# nearsens-schematic-source-2026-05-25-v0_.net
KiCad netlist of a schematic drawn in EasyEDA
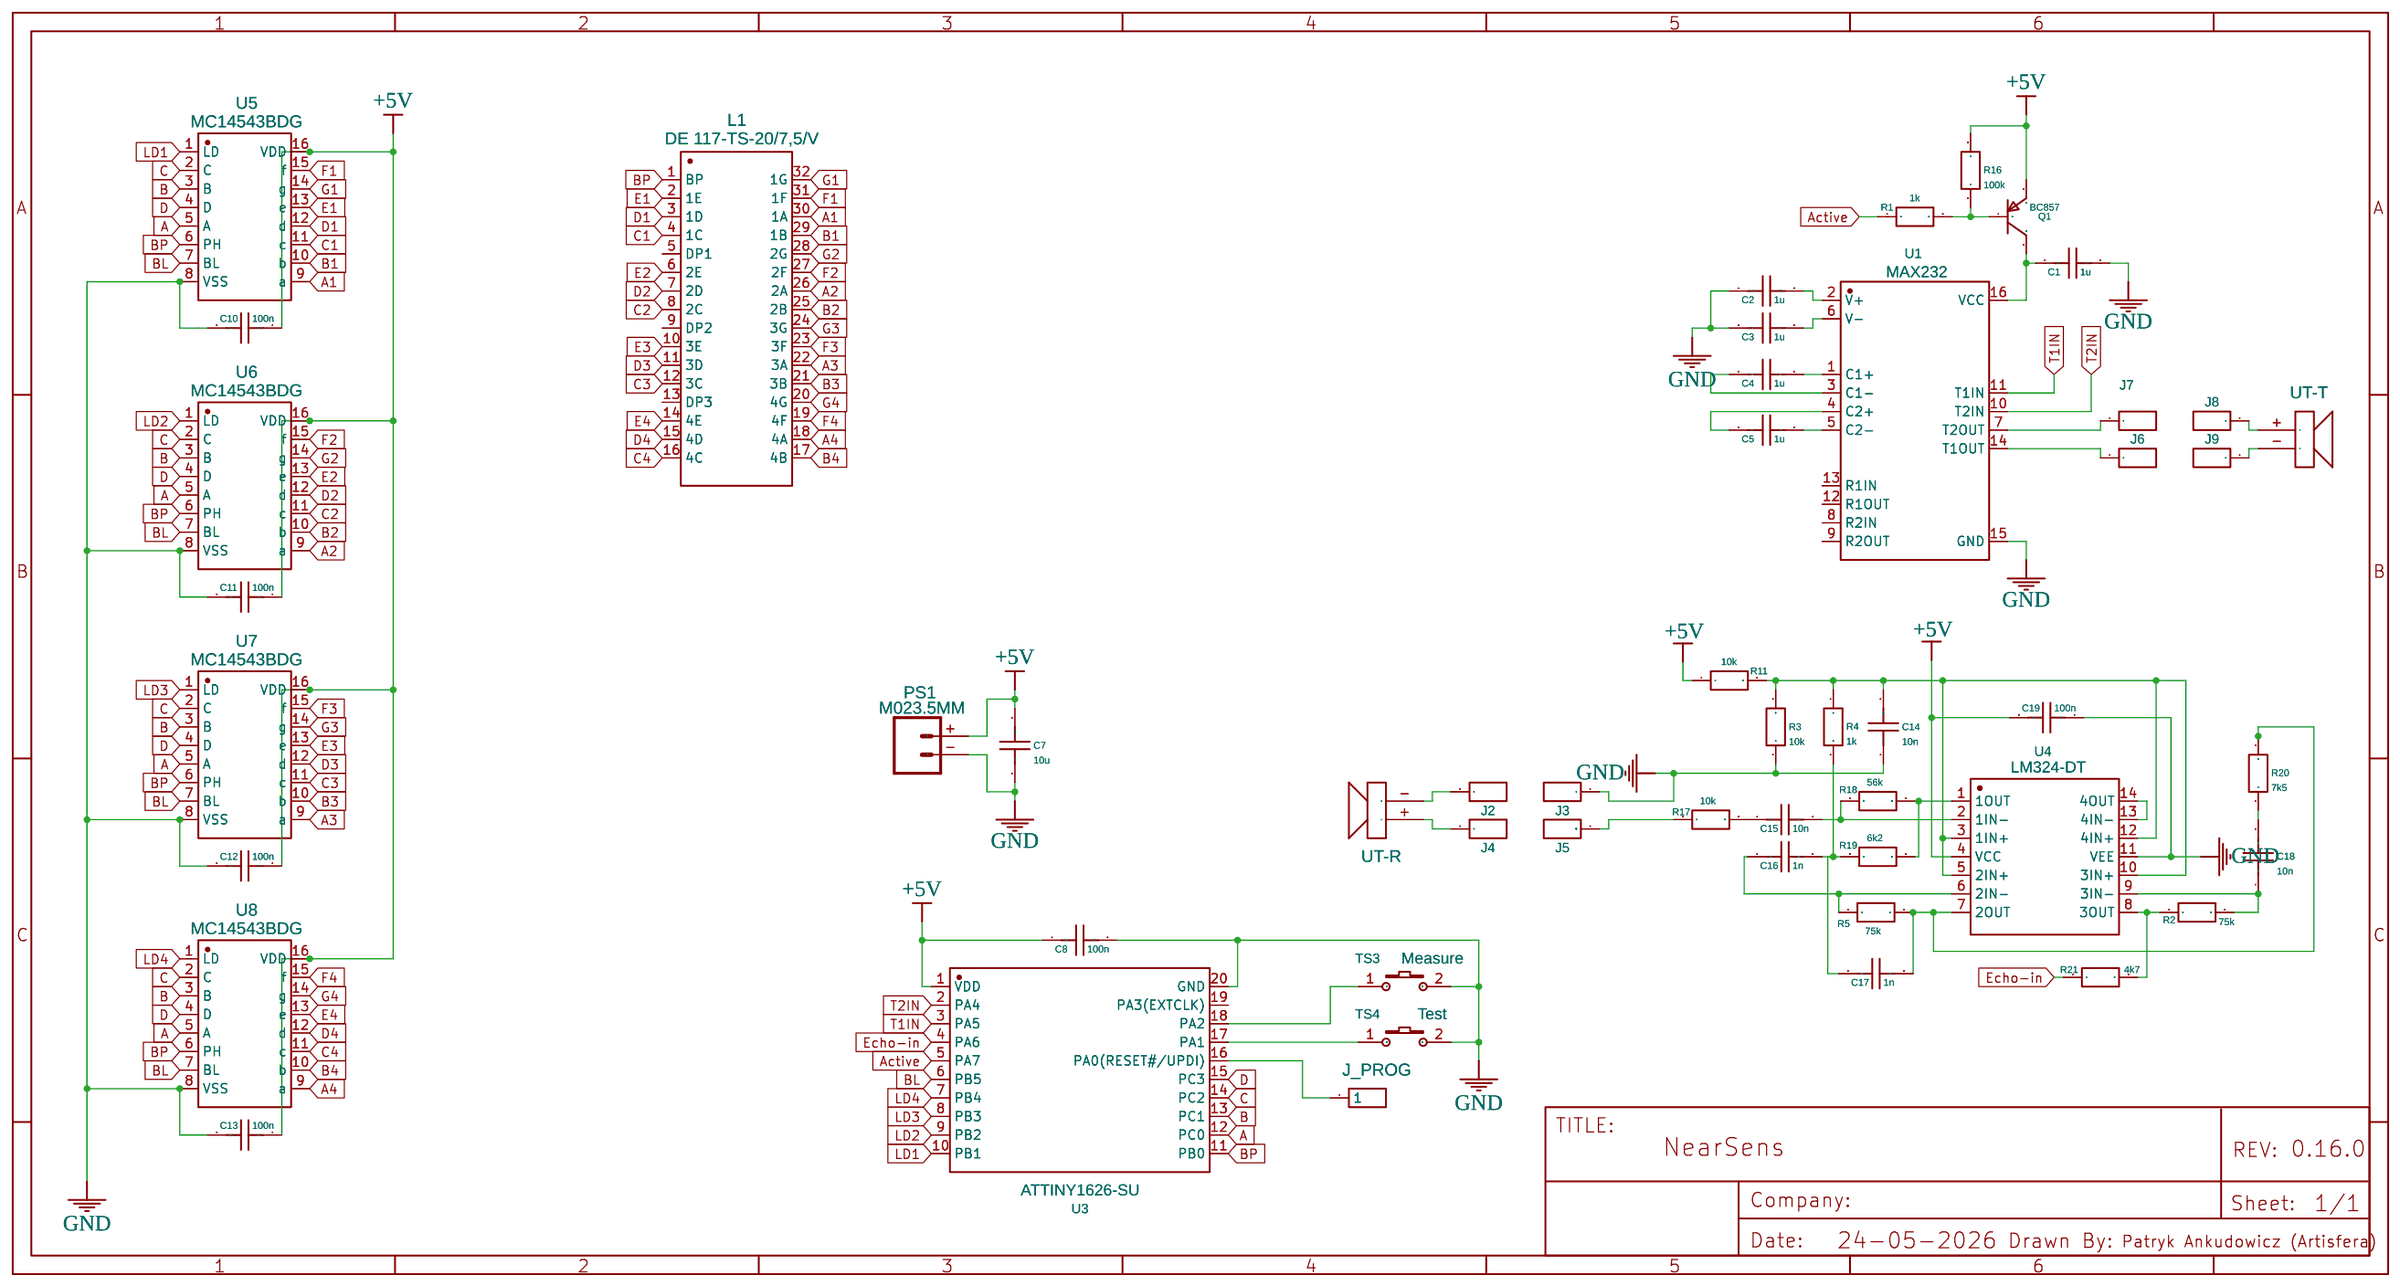
[diagram p0: schematic sheet]

(export (version "E")
  (design (tool "Eeschema 10.0.6"))
  (components
    (comp (ref "C1") (value "1u") (libsource (lib "") (part "C_0603_US_1")))
    (comp (ref "C2") (value "1u") (libsource (lib "") (part "C_0603_US_1")))
    (comp (ref "C3") (value "1u") (libsource (lib "") (part "C_0603_US_1")))
    (comp (ref "C4") (value "1u") (libsource (lib "") (part "C_0603_US_1")))
    (comp (ref "C5") (value "1u") (libsource (lib "") (part "C_0603_US_1")))
    (comp (ref "C7") (value "10u") (libsource (lib "") (part "C_0603_US_3")))
    (comp (ref "C8") (value "100n") (libsource (lib "") (part "C_0603_US_1")))
    (comp (ref "C10") (value "100n") (libsource (lib "") (part "C_0603_US")))
    (comp (ref "C11") (value "100n") (libsource (lib "") (part "C_0603_US")))
    (comp (ref "C12") (value "100n") (libsource (lib "") (part "C_0603_US")))
    (comp (ref "C13") (value "100n") (libsource (lib "") (part "C_0603_US")))
    (comp (ref "C14") (value "10n") (libsource (lib "") (part "C_0603_US_2")))
    (comp (ref "C15") (value "10n") (libsource (lib "") (part "C_0603_US_1")))
    (comp (ref "C16") (value "1n") (libsource (lib "") (part "C_0603_US_1")))
    (comp (ref "C17") (value "1n") (libsource (lib "") (part "C_0603_US_1")))
    (comp (ref "C18") (value "10n") (libsource (lib "") (part "C_0603_US_2")))
    (comp (ref "C19") (value "100n") (libsource (lib "") (part "C_0603_US")))
    (comp (ref "J2") (value "HDR-M-2.54_1x1") (libsource (lib "") (part "HDR-M-2.54_1x1_1")))
    (comp (ref "J3") (value "HDR-M-2.54_1x1") (libsource (lib "") (part "HDR-M-2.54_1x1")))
    (comp (ref "J4") (value "HDR-M-2.54_1x1") (libsource (lib "") (part "HDR-M-2.54_1x1_1")))
    (comp (ref "J5") (value "HDR-M-2.54_1x1") (libsource (lib "") (part "HDR-M-2.54_1x1_2")))
    (comp (ref "J6") (value "HDR-M-2.54_1x1") (libsource (lib "") (part "HDR-M-2.54_1x1_1")))
    (comp (ref "J7") (value "HDR-M-2.54_1x1") (libsource (lib "") (part "HDR-M-2.54_1x1_1")))
    (comp (ref "J8") (value "HDR-M-2.54_1x1") (libsource (lib "") (part "HDR-M-2.54_1x1")))
    (comp (ref "J9") (value "HDR-M-2.54_1x1") (libsource (lib "") (part "HDR-M-2.54_1x1")))
    (comp (ref "J_PROG") (value "Programming") (libsource (lib "") (part "HDR-M-2.54_1x1_3")))
    (comp (ref "L1")
      (value "DE 117-TS-20/7,5/V")
      (fields (field (name "Manufacturer") "DISPLAY ELEKTRONIK"))
      (libsource (lib "") (part "DE 117-TS-20/7,5/V DISPLAY ELEKTRONIK - Display LCD"))
    )
    (comp (ref "PS1") (value "M023.5MM") (libsource (lib "") (part "M023.5MM")))
    (comp (ref "Q1")
      (value "BC857")
      (fields
        (field (name "Manufacturer Part") "BC557(RANGE:420-800)")
        (field (name "Manufacturer") "CJ(江苏长电/长晶)")
      )
      (libsource (lib "") (part "BC557"))
    )
    (comp (ref "R1") (value "1k") (libsource (lib "") (part "R_0603_EU")))
    (comp (ref "R2") (value "75k") (libsource (lib "") (part "R_0603_EU")))
    (comp (ref "R3") (value "10k") (libsource (lib "") (part "R_0603_EU_1")))
    (comp (ref "R4") (value "1k") (libsource (lib "") (part "R_0603_EU_2")))
    (comp (ref "R5") (value "75k") (libsource (lib "") (part "R_0603_EU")))
    (comp (ref "R11") (value "10k") (libsource (lib "") (part "R_0603_EU")))
    (comp (ref "R16") (value "100k") (libsource (lib "") (part "R_0603_EU_1")))
    (comp (ref "R17") (value "10k") (libsource (lib "") (part "R_0603_EU")))
    (comp (ref "R18") (value "56k") (libsource (lib "") (part "R_0603_EU")))
    (comp (ref "R19") (value "6k2") (libsource (lib "") (part "R_0603_EU")))
    (comp (ref "R20") (value "7k5") (libsource (lib "") (part "R_0603_EU_1")))
    (comp (ref "R21") (value "4k7") (libsource (lib "") (part "R_0603_EU")))
    (comp (ref "TS3")
      (value "Measure")
      (fields (field (name "Manufacturer Part") "K2-1107ST-A4SW-06"))
      (libsource (lib "") (part "K2-3.6×6.1_SMD"))
    )
    (comp (ref "TS4")
      (value "Test")
      (fields (field (name "Manufacturer Part") "K2-1107ST-A4SW-06"))
      (libsource (lib "") (part "K2-3.6×6.1_SMD"))
    )
    (comp (ref "U1")
      (value "MAX232")
      (fields (field (name "Manufacturer Part") "MAX232ESE-EV") (field (name "Manufacturer") "EVVO(翊欧)"))
      (libsource (lib "") (part "MAX232ESE-EV"))
    )
    (comp (ref "U3")
      (value "ATTINY1626-SU")
      (fields (field (name "Manufacturer") "MICROCHIP(美国微芯)"))
      (libsource (lib "") (part "ATTINY1626-SU"))
    )
    (comp (ref "U4")
      (value "LM324-DT")
      (fields (field (name "Manufacturer Part") "LM324-DW") (field (name "Manufacturer") "DOWO(东沃)"))
      (libsource (lib "") (part "LM324-DW"))
    )
    (comp (ref "U5") (value "MC14543BDG") (libsource (lib "") (part "MC14543BDG")))
    (comp (ref "U6") (value "MC14543BDG") (libsource (lib "") (part "MC14543BDG")))
    (comp (ref "U7") (value "MC14543BDG") (libsource (lib "") (part "MC14543BDG")))
    (comp (ref "U8") (value "MC14543BDG") (libsource (lib "") (part "MC14543BDG")))
    (comp (ref "UT-R")
      (value "Przetwornik ultradzwiekowy")
      (fields (field (name "Manufacturer Part") "I47123") (field (name "Manufacturer") "I47"))
      (libsource (lib "") (part "ULTRASONIC TRANSDUCER_1"))
    )
    (comp (ref "UT-T")
      (value "Przetwornik ultradzwiekowy")
      (fields (field (name "Manufacturer Part") "I47123") (field (name "Manufacturer") "I47"))
      (libsource (lib "") (part "ULTRASONIC TRANSDUCER"))
    )
  )
  (nets
    (net (code "1") (name "+5V") (class "Default")
      (node (ref "C10") (pin "1") (pinfunction "1_1") (pintype "unspecified"))
      (node (ref "C11") (pin "1") (pinfunction "1_1") (pintype "unspecified"))
      (node (ref "C12") (pin "1") (pinfunction "1_1") (pintype "unspecified"))
      (node (ref "C13") (pin "1") (pinfunction "1_1") (pintype "unspecified"))
      (node (ref "C19") (pin "2") (pinfunction "2_2") (pintype "unspecified"))
      (node (ref "C7") (pin "1") (pinfunction "1_1") (pintype "unspecified"))
      (node (ref "C8") (pin "1") (pinfunction "1_1") (pintype "unspecified"))
      (node (ref "PS1") (pin "+") (pinfunction "2_+") (pintype "bidirectional"))
      (node (ref "Q1") (pin "2") (pinfunction "E_2") (pintype "unspecified"))
      (node (ref "R11") (pin "1") (pinfunction "1_1") (pintype "unspecified"))
      (node (ref "R16") (pin "2") (pinfunction "2_2") (pintype "unspecified"))
      (node (ref "U3") (pin "1") (pinfunction "VDD_1") (pintype "unspecified"))
      (node (ref "U4") (pin "4") (pinfunction "VCC_4") (pintype "unspecified"))
      (node (ref "U5") (pin "16") (pinfunction "VDD_16") (pintype "unspecified"))
      (node (ref "U6") (pin "16") (pinfunction "VDD_16") (pintype "unspecified"))
      (node (ref "U7") (pin "16") (pinfunction "VDD_16") (pintype "unspecified"))
      (node (ref "U8") (pin "16") (pinfunction "VDD_16") (pintype "unspecified"))
    )
    (net (code "2") (name "A") (class "Default")
      (node (ref "U3") (pin "12") (pinfunction "PC0_12") (pintype "unspecified"))
      (node (ref "U5") (pin "5") (pinfunction "A_5") (pintype "unspecified"))
      (node (ref "U6") (pin "5") (pinfunction "A_5") (pintype "unspecified"))
      (node (ref "U7") (pin "5") (pinfunction "A_5") (pintype "unspecified"))
      (node (ref "U8") (pin "5") (pinfunction "A_5") (pintype "unspecified"))
    )
    (net (code "3") (name "A1") (class "Default")
      (node (ref "L1") (pin "30") (pinfunction "1A_30") (pintype "unspecified"))
      (node (ref "U5") (pin "9") (pinfunction "a_9") (pintype "unspecified"))
    )
    (net (code "4") (name "A2") (class "Default")
      (node (ref "L1") (pin "26") (pinfunction "2A_26") (pintype "unspecified"))
      (node (ref "U6") (pin "9") (pinfunction "a_9") (pintype "unspecified"))
    )
    (net (code "5") (name "A3") (class "Default")
      (node (ref "L1") (pin "22") (pinfunction "3A_22") (pintype "unspecified"))
      (node (ref "U7") (pin "9") (pinfunction "a_9") (pintype "unspecified"))
    )
    (net (code "6") (name "A4") (class "Default")
      (node (ref "L1") (pin "18") (pinfunction "4A_18") (pintype "unspecified"))
      (node (ref "U8") (pin "9") (pinfunction "a_9") (pintype "unspecified"))
    )
    (net (code "7") (name "Active") (class "Default")
      (node (ref "R1") (pin "1") (pinfunction "1_1") (pintype "unspecified"))
      (node (ref "U3") (pin "5") (pinfunction "PA7_5") (pintype "unspecified"))
    )
    (net (code "8") (name "B") (class "Default")
      (node (ref "U3") (pin "13") (pinfunction "PC1_13") (pintype "unspecified"))
      (node (ref "U5") (pin "3") (pinfunction "B_3") (pintype "unspecified"))
      (node (ref "U6") (pin "3") (pinfunction "B_3") (pintype "unspecified"))
      (node (ref "U7") (pin "3") (pinfunction "B_3") (pintype "unspecified"))
      (node (ref "U8") (pin "3") (pinfunction "B_3") (pintype "unspecified"))
    )
    (net (code "9") (name "B1") (class "Default")
      (node (ref "L1") (pin "29") (pinfunction "1B_29") (pintype "unspecified"))
      (node (ref "U5") (pin "10") (pinfunction "b_10") (pintype "unspecified"))
    )
    (net (code "10") (name "B2") (class "Default")
      (node (ref "L1") (pin "25") (pinfunction "2B_25") (pintype "unspecified"))
      (node (ref "U6") (pin "10") (pinfunction "b_10") (pintype "unspecified"))
    )
    (net (code "11") (name "B3") (class "Default")
      (node (ref "L1") (pin "21") (pinfunction "3B_21") (pintype "unspecified"))
      (node (ref "U7") (pin "10") (pinfunction "b_10") (pintype "unspecified"))
    )
    (net (code "12") (name "B4") (class "Default")
      (node (ref "L1") (pin "17") (pinfunction "4B_17") (pintype "unspecified"))
      (node (ref "U8") (pin "10") (pinfunction "b_10") (pintype "unspecified"))
    )
    (net (code "13") (name "BL") (class "Default")
      (node (ref "U3") (pin "6") (pinfunction "PB5_6") (pintype "unspecified"))
      (node (ref "U5") (pin "7") (pinfunction "BL_7") (pintype "unspecified"))
      (node (ref "U6") (pin "7") (pinfunction "BL_7") (pintype "unspecified"))
      (node (ref "U7") (pin "7") (pinfunction "BL_7") (pintype "unspecified"))
      (node (ref "U8") (pin "7") (pinfunction "BL_7") (pintype "unspecified"))
    )
    (net (code "14") (name "BP") (class "Default")
      (node (ref "L1") (pin "1") (pinfunction "BP_1") (pintype "unspecified"))
      (node (ref "U3") (pin "11") (pinfunction "PB0_11") (pintype "unspecified"))
      (node (ref "U5") (pin "6") (pinfunction "PH_6") (pintype "unspecified"))
      (node (ref "U6") (pin "6") (pinfunction "PH_6") (pintype "unspecified"))
      (node (ref "U7") (pin "6") (pinfunction "PH_6") (pintype "unspecified"))
      (node (ref "U8") (pin "6") (pinfunction "PH_6") (pintype "unspecified"))
    )
    (net (code "15") (name "C") (class "Default")
      (node (ref "U3") (pin "14") (pinfunction "PC2_14") (pintype "unspecified"))
      (node (ref "U5") (pin "2") (pinfunction "C_2") (pintype "unspecified"))
      (node (ref "U6") (pin "2") (pinfunction "C_2") (pintype "unspecified"))
      (node (ref "U7") (pin "2") (pinfunction "C_2") (pintype "unspecified"))
      (node (ref "U8") (pin "2") (pinfunction "C_2") (pintype "unspecified"))
    )
    (net (code "16") (name "C1") (class "Default")
      (node (ref "L1") (pin "4") (pinfunction "1C_4") (pintype "unspecified"))
      (node (ref "U5") (pin "11") (pinfunction "c_11") (pintype "unspecified"))
    )
    (net (code "17") (name "C2") (class "Default")
      (node (ref "L1") (pin "8") (pinfunction "2C_8") (pintype "unspecified"))
      (node (ref "U6") (pin "11") (pinfunction "c_11") (pintype "unspecified"))
    )
    (net (code "18") (name "C3") (class "Default")
      (node (ref "L1") (pin "12") (pinfunction "3C_12") (pintype "unspecified"))
      (node (ref "U7") (pin "11") (pinfunction "c_11") (pintype "unspecified"))
    )
    (net (code "19") (name "C4") (class "Default")
      (node (ref "L1") (pin "16") (pinfunction "4C_16") (pintype "unspecified"))
      (node (ref "U8") (pin "11") (pinfunction "c_11") (pintype "unspecified"))
    )
    (net (code "20") (name "D") (class "Default")
      (node (ref "U3") (pin "15") (pinfunction "PC3_15") (pintype "unspecified"))
      (node (ref "U5") (pin "4") (pinfunction "D_4") (pintype "unspecified"))
      (node (ref "U6") (pin "4") (pinfunction "D_4") (pintype "unspecified"))
      (node (ref "U7") (pin "4") (pinfunction "D_4") (pintype "unspecified"))
      (node (ref "U8") (pin "4") (pinfunction "D_4") (pintype "unspecified"))
    )
    (net (code "21") (name "D1") (class "Default")
      (node (ref "L1") (pin "3") (pinfunction "1D_3") (pintype "unspecified"))
      (node (ref "U5") (pin "12") (pinfunction "d_12") (pintype "unspecified"))
    )
    (net (code "22") (name "D2") (class "Default")
      (node (ref "L1") (pin "7") (pinfunction "2D_7") (pintype "unspecified"))
      (node (ref "U6") (pin "12") (pinfunction "d_12") (pintype "unspecified"))
    )
    (net (code "23") (name "D3") (class "Default")
      (node (ref "L1") (pin "11") (pinfunction "3D_11") (pintype "unspecified"))
      (node (ref "U7") (pin "12") (pinfunction "d_12") (pintype "unspecified"))
    )
    (net (code "24") (name "D4") (class "Default")
      (node (ref "L1") (pin "15") (pinfunction "4D_15") (pintype "unspecified"))
      (node (ref "U8") (pin "12") (pinfunction "d_12") (pintype "unspecified"))
    )
    (net (code "25") (name "E1") (class "Default")
      (node (ref "L1") (pin "2") (pinfunction "1E_2") (pintype "unspecified"))
      (node (ref "U5") (pin "13") (pinfunction "e_13") (pintype "unspecified"))
    )
    (net (code "26") (name "E2") (class "Default")
      (node (ref "L1") (pin "6") (pinfunction "2E_6") (pintype "unspecified"))
      (node (ref "U6") (pin "13") (pinfunction "e_13") (pintype "unspecified"))
    )
    (net (code "27") (name "E3") (class "Default")
      (node (ref "L1") (pin "10") (pinfunction "3E_10") (pintype "unspecified"))
      (node (ref "U7") (pin "13") (pinfunction "e_13") (pintype "unspecified"))
    )
    (net (code "28") (name "E4") (class "Default")
      (node (ref "L1") (pin "14") (pinfunction "4E_14") (pintype "unspecified"))
      (node (ref "U8") (pin "13") (pinfunction "e_13") (pintype "unspecified"))
    )
    (net (code "29") (name "Echo-in") (class "Default")
      (node (ref "R21") (pin "1") (pinfunction "1_1") (pintype "unspecified"))
      (node (ref "U3") (pin "4") (pinfunction "PA6_4") (pintype "unspecified"))
    )
    (net (code "30") (name "F1") (class "Default")
      (node (ref "L1") (pin "31") (pinfunction "1F_31") (pintype "unspecified"))
      (node (ref "U5") (pin "15") (pinfunction "f_15") (pintype "unspecified"))
    )
    (net (code "31") (name "F2") (class "Default")
      (node (ref "L1") (pin "27") (pinfunction "2F_27") (pintype "unspecified"))
      (node (ref "U6") (pin "15") (pinfunction "f_15") (pintype "unspecified"))
    )
    (net (code "32") (name "F3") (class "Default")
      (node (ref "L1") (pin "23") (pinfunction "3F_23") (pintype "unspecified"))
      (node (ref "U7") (pin "15") (pinfunction "f_15") (pintype "unspecified"))
    )
    (net (code "33") (name "F4") (class "Default")
      (node (ref "L1") (pin "19") (pinfunction "4F_19") (pintype "unspecified"))
      (node (ref "U8") (pin "15") (pinfunction "f_15") (pintype "unspecified"))
    )
    (net (code "34") (name "G1") (class "Default")
      (node (ref "L1") (pin "32") (pinfunction "1G_32") (pintype "unspecified"))
      (node (ref "U5") (pin "14") (pinfunction "g_14") (pintype "unspecified"))
    )
    (net (code "35") (name "G2") (class "Default")
      (node (ref "L1") (pin "28") (pinfunction "2G_28") (pintype "unspecified"))
      (node (ref "U6") (pin "14") (pinfunction "g_14") (pintype "unspecified"))
    )
    (net (code "36") (name "G3") (class "Default")
      (node (ref "L1") (pin "24") (pinfunction "3G_24") (pintype "unspecified"))
      (node (ref "U7") (pin "14") (pinfunction "g_14") (pintype "unspecified"))
    )
    (net (code "37") (name "G4") (class "Default")
      (node (ref "L1") (pin "20") (pinfunction "4G_20") (pintype "unspecified"))
      (node (ref "U8") (pin "14") (pinfunction "g_14") (pintype "unspecified"))
    )
    (net (code "38") (name "GND") (class "Default")
      (node (ref "C1") (pin "2") (pinfunction "2_2") (pintype "unspecified"))
      (node (ref "C10") (pin "2") (pinfunction "2_2") (pintype "unspecified"))
      (node (ref "C11") (pin "2") (pinfunction "2_2") (pintype "unspecified"))
      (node (ref "C12") (pin "2") (pinfunction "2_2") (pintype "unspecified"))
      (node (ref "C13") (pin "2") (pinfunction "2_2") (pintype "unspecified"))
      (node (ref "C14") (pin "1") (pinfunction "1_1") (pintype "unspecified"))
      (node (ref "C19") (pin "1") (pinfunction "1_1") (pintype "unspecified"))
      (node (ref "C2") (pin "1") (pinfunction "1_1") (pintype "unspecified"))
      (node (ref "C3") (pin "1") (pinfunction "1_1") (pintype "unspecified"))
      (node (ref "C7") (pin "2") (pinfunction "2_2") (pintype "unspecified"))
      (node (ref "C8") (pin "2") (pinfunction "2_2") (pintype "unspecified"))
      (node (ref "J3") (pin "1") (pinfunction "1_1") (pintype "input"))
      (node (ref "PS1") (pin "-") (pinfunction "1_-") (pintype "bidirectional"))
      (node (ref "R3") (pin "1") (pinfunction "1_1") (pintype "unspecified"))
      (node (ref "TS3") (pin "2") (pinfunction "2_2") (pintype "unspecified"))
      (node (ref "TS4") (pin "2") (pinfunction "2_2") (pintype "unspecified"))
      (node (ref "U1") (pin "15") (pinfunction "GND_15") (pintype "unspecified"))
      (node (ref "U3") (pin "20") (pinfunction "GND_20") (pintype "unspecified"))
      (node (ref "U4") (pin "11") (pinfunction "VEE_11") (pintype "unspecified"))
      (node (ref "U5") (pin "8") (pinfunction "VSS_8") (pintype "unspecified"))
      (node (ref "U6") (pin "8") (pinfunction "VSS_8") (pintype "unspecified"))
      (node (ref "U7") (pin "8") (pinfunction "VSS_8") (pintype "unspecified"))
      (node (ref "U8") (pin "8") (pinfunction "VSS_8") (pintype "unspecified"))
    )
    (net (code "39") (name "LD1") (class "Default")
      (node (ref "U3") (pin "10") (pinfunction "PB1_10") (pintype "unspecified"))
      (node (ref "U5") (pin "1") (pinfunction "LD_1") (pintype "unspecified"))
    )
    (net (code "40") (name "LD2") (class "Default")
      (node (ref "U3") (pin "9") (pinfunction "PB2_9") (pintype "unspecified"))
      (node (ref "U6") (pin "1") (pinfunction "LD_1") (pintype "unspecified"))
    )
    (net (code "41") (name "LD3") (class "Default")
      (node (ref "U3") (pin "8") (pinfunction "PB3_8") (pintype "unspecified"))
      (node (ref "U7") (pin "1") (pinfunction "LD_1") (pintype "unspecified"))
    )
    (net (code "42") (name "LD4") (class "Default")
      (node (ref "U3") (pin "7") (pinfunction "PB4_7") (pintype "unspecified"))
      (node (ref "U8") (pin "1") (pinfunction "LD_1") (pintype "unspecified"))
    )
    (net (code "43") (name "Net-(C15-Pad1)") (class "Default")
      (node (ref "C15") (pin "1") (pinfunction "1_1") (pintype "unspecified"))
      (node (ref "R17") (pin "2") (pinfunction "2_2") (pintype "unspecified"))
    )
    (net (code "44") (name "Net-(C16-Pad2)") (class "Default")
      (node (ref "C16") (pin "2") (pinfunction "2_2") (pintype "unspecified"))
      (node (ref "C17") (pin "1") (pinfunction "1_1") (pintype "unspecified"))
      (node (ref "R19") (pin "1") (pinfunction "1_1") (pintype "unspecified"))
      (node (ref "R4") (pin "2") (pinfunction "2_2") (pintype "unspecified"))
    )
    (net (code "45") (name "Net-(C18-Pad2)") (class "Default")
      (node (ref "C18") (pin "2") (pinfunction "2_2") (pintype "unspecified"))
      (node (ref "R20") (pin "1") (pinfunction "1_1") (pintype "unspecified"))
    )
    (net (code "46") (name "Net-(J5-PAD)") (class "Default")
      (node (ref "J5") (pin "1") (pinfunction "PAD_1") (pintype "input"))
      (node (ref "R17") (pin "1") (pinfunction "1_1") (pintype "unspecified"))
    )
    (net (code "47") (name "Net-(Q1-B)") (class "Default")
      (node (ref "Q1") (pin "1") (pinfunction "B_1") (pintype "unspecified"))
      (node (ref "R1") (pin "2") (pinfunction "2_2") (pintype "unspecified"))
      (node (ref "R16") (pin "1") (pinfunction "1_1") (pintype "unspecified"))
    )
    (net (code "48") (name "Net-(Q1-C)") (class "Default")
      (node (ref "C1") (pin "1") (pinfunction "1_1") (pintype "unspecified"))
      (node (ref "Q1") (pin "3") (pinfunction "C_3") (pintype "unspecified"))
      (node (ref "U1") (pin "16") (pinfunction "VCC_16") (pintype "unspecified"))
    )
    (net (code "49") (name "Net-(U1-C1+)") (class "Default")
      (node (ref "C4") (pin "2") (pinfunction "2_2") (pintype "unspecified"))
      (node (ref "U1") (pin "1") (pinfunction "C1+_1") (pintype "unspecified"))
    )
    (net (code "50") (name "Net-(U1-C1-)") (class "Default")
      (node (ref "C4") (pin "1") (pinfunction "1_1") (pintype "unspecified"))
      (node (ref "U1") (pin "3") (pinfunction "C1-_3") (pintype "unspecified"))
    )
    (net (code "51") (name "Net-(U1-C2+)") (class "Default")
      (node (ref "C5") (pin "1") (pinfunction "1_1") (pintype "unspecified"))
      (node (ref "U1") (pin "4") (pinfunction "C2+_4") (pintype "unspecified"))
    )
    (net (code "52") (name "Net-(U1-C2-)") (class "Default")
      (node (ref "C5") (pin "2") (pinfunction "2_2") (pintype "unspecified"))
      (node (ref "U1") (pin "5") (pinfunction "C2-_5") (pintype "unspecified"))
    )
    (net (code "53") (name "Net-(U1-T1OUT)") (class "Default")
      (node (ref "J6") (pin "1") (pinfunction "1_1") (pintype "input"))
      (node (ref "U1") (pin "14") (pinfunction "T1OUT_14") (pintype "unspecified"))
    )
    (net (code "54") (name "Net-(U1-T2OUT)") (class "Default")
      (node (ref "J7") (pin "1") (pinfunction "1_1") (pintype "input"))
      (node (ref "U1") (pin "7") (pinfunction "T2OUT_7") (pintype "unspecified"))
    )
    (net (code "55") (name "Net-(U1-V+)") (class "Default")
      (node (ref "C2") (pin "2") (pinfunction "2_2") (pintype "unspecified"))
      (node (ref "U1") (pin "2") (pinfunction "V+_2") (pintype "unspecified"))
    )
    (net (code "56") (name "Net-(U1-V-)") (class "Default")
      (node (ref "C3") (pin "2") (pinfunction "2_2") (pintype "unspecified"))
      (node (ref "U1") (pin "6") (pinfunction "V-_6") (pintype "unspecified"))
    )
    (net (code "57") (name "Net-(U3-PA0(RESET#{slash}UPDI))") (class "Default")
      (node (ref "J_PROG") (pin "1") (pinfunction "1_1") (pintype "input"))
      (node (ref "U3") (pin "16") (pinfunction "PA0(RESET#/UPDI)_16") (pintype "unspecified"))
    )
    (net (code "58") (name "Net-(U3-PA1)") (class "Default")
      (node (ref "TS4") (pin "1") (pinfunction "1_1") (pintype "unspecified"))
      (node (ref "U3") (pin "17") (pinfunction "PA1_17") (pintype "unspecified"))
    )
    (net (code "59") (name "Net-(U3-PA2)") (class "Default")
      (node (ref "TS3") (pin "1") (pinfunction "1_1") (pintype "unspecified"))
      (node (ref "U3") (pin "18") (pinfunction "PA2_18") (pintype "unspecified"))
    )
    (net (code "60") (name "Net-(U4-1IN+)") (class "Default")
      (node (ref "C14") (pin "2") (pinfunction "2_2") (pintype "unspecified"))
      (node (ref "R11") (pin "2") (pinfunction "2_2") (pintype "unspecified"))
      (node (ref "R3") (pin "2") (pinfunction "2_2") (pintype "unspecified"))
      (node (ref "R4") (pin "1") (pinfunction "1_1") (pintype "unspecified"))
      (node (ref "U4") (pin "10") (pinfunction "3IN+_10") (pintype "unspecified"))
      (node (ref "U4") (pin "12") (pinfunction "4IN+_12") (pintype "unspecified"))
      (node (ref "U4") (pin "3") (pinfunction "1IN+_3") (pintype "unspecified"))
      (node (ref "U4") (pin "5") (pinfunction "2IN+_5") (pintype "unspecified"))
    )
    (net (code "61") (name "Net-(U4-1IN-)") (class "Default")
      (node (ref "C15") (pin "2") (pinfunction "2_2") (pintype "unspecified"))
      (node (ref "R18") (pin "1") (pinfunction "1_1") (pintype "unspecified"))
      (node (ref "U4") (pin "2") (pinfunction "1IN-_2") (pintype "unspecified"))
    )
    (net (code "62") (name "Net-(U4-1OUT)") (class "Default")
      (node (ref "R18") (pin "2") (pinfunction "2_2") (pintype "unspecified"))
      (node (ref "R19") (pin "2") (pinfunction "2_2") (pintype "unspecified"))
      (node (ref "U4") (pin "1") (pinfunction "1OUT_1") (pintype "unspecified"))
    )
    (net (code "63") (name "Net-(U4-2IN-)") (class "Default")
      (node (ref "C16") (pin "1") (pinfunction "1_1") (pintype "unspecified"))
      (node (ref "R5") (pin "1") (pinfunction "1_1") (pintype "unspecified"))
      (node (ref "U4") (pin "6") (pinfunction "2IN-_6") (pintype "unspecified"))
    )
    (net (code "64") (name "Net-(U4-2OUT)") (class "Default")
      (node (ref "C17") (pin "2") (pinfunction "2_2") (pintype "unspecified"))
      (node (ref "R20") (pin "2") (pinfunction "2_2") (pintype "unspecified"))
      (node (ref "R5") (pin "2") (pinfunction "2_2") (pintype "unspecified"))
      (node (ref "U4") (pin "7") (pinfunction "2OUT_7") (pintype "unspecified"))
    )
    (net (code "65") (name "Net-(U4-3IN-)") (class "Default")
      (node (ref "C18") (pin "1") (pinfunction "1_1") (pintype "unspecified"))
      (node (ref "R2") (pin "2") (pinfunction "2_2") (pintype "unspecified"))
      (node (ref "U4") (pin "9") (pinfunction "3IN-_9") (pintype "unspecified"))
    )
    (net (code "66") (name "Net-(U4-3OUT)") (class "Default")
      (node (ref "R2") (pin "1") (pinfunction "1_1") (pintype "unspecified"))
      (node (ref "R21") (pin "2") (pinfunction "2_2") (pintype "unspecified"))
      (node (ref "U4") (pin "8") (pinfunction "3OUT_8") (pintype "unspecified"))
    )
    (net (code "67") (name "Net-(U4-4IN-)") (class "Default")
      (node (ref "U4") (pin "13") (pinfunction "4IN-_13") (pintype "unspecified"))
      (node (ref "U4") (pin "14") (pinfunction "4OUT_14") (pintype "unspecified"))
    )
    (net (code "68") (name "Net-(UT-R-+)") (class "Default")
      (node (ref "J2") (pin "1") (pinfunction "1_1") (pintype "input"))
      (node (ref "UT-R") (pin "-") (pinfunction "+_-") (pintype "bidirectional"))
    )
    (net (code "69") (name "Net-(UT-R--)") (class "Default")
      (node (ref "J4") (pin "1") (pinfunction "1_1") (pintype "input"))
      (node (ref "UT-R") (pin "+") (pinfunction "-_+") (pintype "bidirectional"))
    )
    (net (code "70") (name "Net-(UT-T-+)") (class "Default")
      (node (ref "J9") (pin "1") (pinfunction "1_1") (pintype "input"))
      (node (ref "UT-T") (pin "-") (pinfunction "+_-") (pintype "bidirectional"))
    )
    (net (code "71") (name "Net-(UT-T--)") (class "Default")
      (node (ref "J8") (pin "1") (pinfunction "1_1") (pintype "input"))
      (node (ref "UT-T") (pin "+") (pinfunction "-_+") (pintype "bidirectional"))
    )
    (net (code "72") (name "T1IN") (class "Default")
      (node (ref "U1") (pin "11") (pinfunction "T1IN_11") (pintype "unspecified"))
      (node (ref "U3") (pin "3") (pinfunction "PA5_3") (pintype "unspecified"))
    )
    (net (code "73") (name "T2IN") (class "Default")
      (node (ref "U1") (pin "10") (pinfunction "T2IN_10") (pintype "unspecified"))
      (node (ref "U3") (pin "2") (pinfunction "PA4_2") (pintype "unspecified"))
    )
    (net (code "74") (name "unconnected-(L1-DP1-Pad5)") (class "Default")
      (node (ref "L1") (pin "5") (pinfunction "DP1_5") (pintype "unspecified"))
    )
    (net (code "75") (name "unconnected-(L1-DP2-Pad9)") (class "Default")
      (node (ref "L1") (pin "9") (pinfunction "DP2_9") (pintype "unspecified"))
    )
    (net (code "76") (name "unconnected-(L1-DP3-Pad13)") (class "Default")
      (node (ref "L1") (pin "13") (pinfunction "DP3_13") (pintype "unspecified"))
    )
    (net (code "77") (name "unconnected-(U1-R1IN-Pad13)") (class "Default")
      (node (ref "U1") (pin "13") (pinfunction "R1IN_13") (pintype "unspecified"))
    )
    (net (code "78") (name "unconnected-(U1-R1OUT-Pad12)") (class "Default")
      (node (ref "U1") (pin "12") (pinfunction "R1OUT_12") (pintype "unspecified"))
    )
    (net (code "79") (name "unconnected-(U1-R2IN-Pad8)") (class "Default")
      (node (ref "U1") (pin "8") (pinfunction "R2IN_8") (pintype "unspecified"))
    )
    (net (code "80") (name "unconnected-(U1-R2OUT-Pad9)") (class "Default")
      (node (ref "U1") (pin "9") (pinfunction "R2OUT_9") (pintype "unspecified"))
    )
    (net (code "81") (name "unconnected-(U3-PA3(EXTCLK)-Pad19)") (class "Default")
      (node (ref "U3") (pin "19") (pinfunction "PA3(EXTCLK)_19") (pintype "unspecified"))
    )
  )
)
